# psvemmc-v12.net
KiCad netlist of a schematic drawn in EAGLE
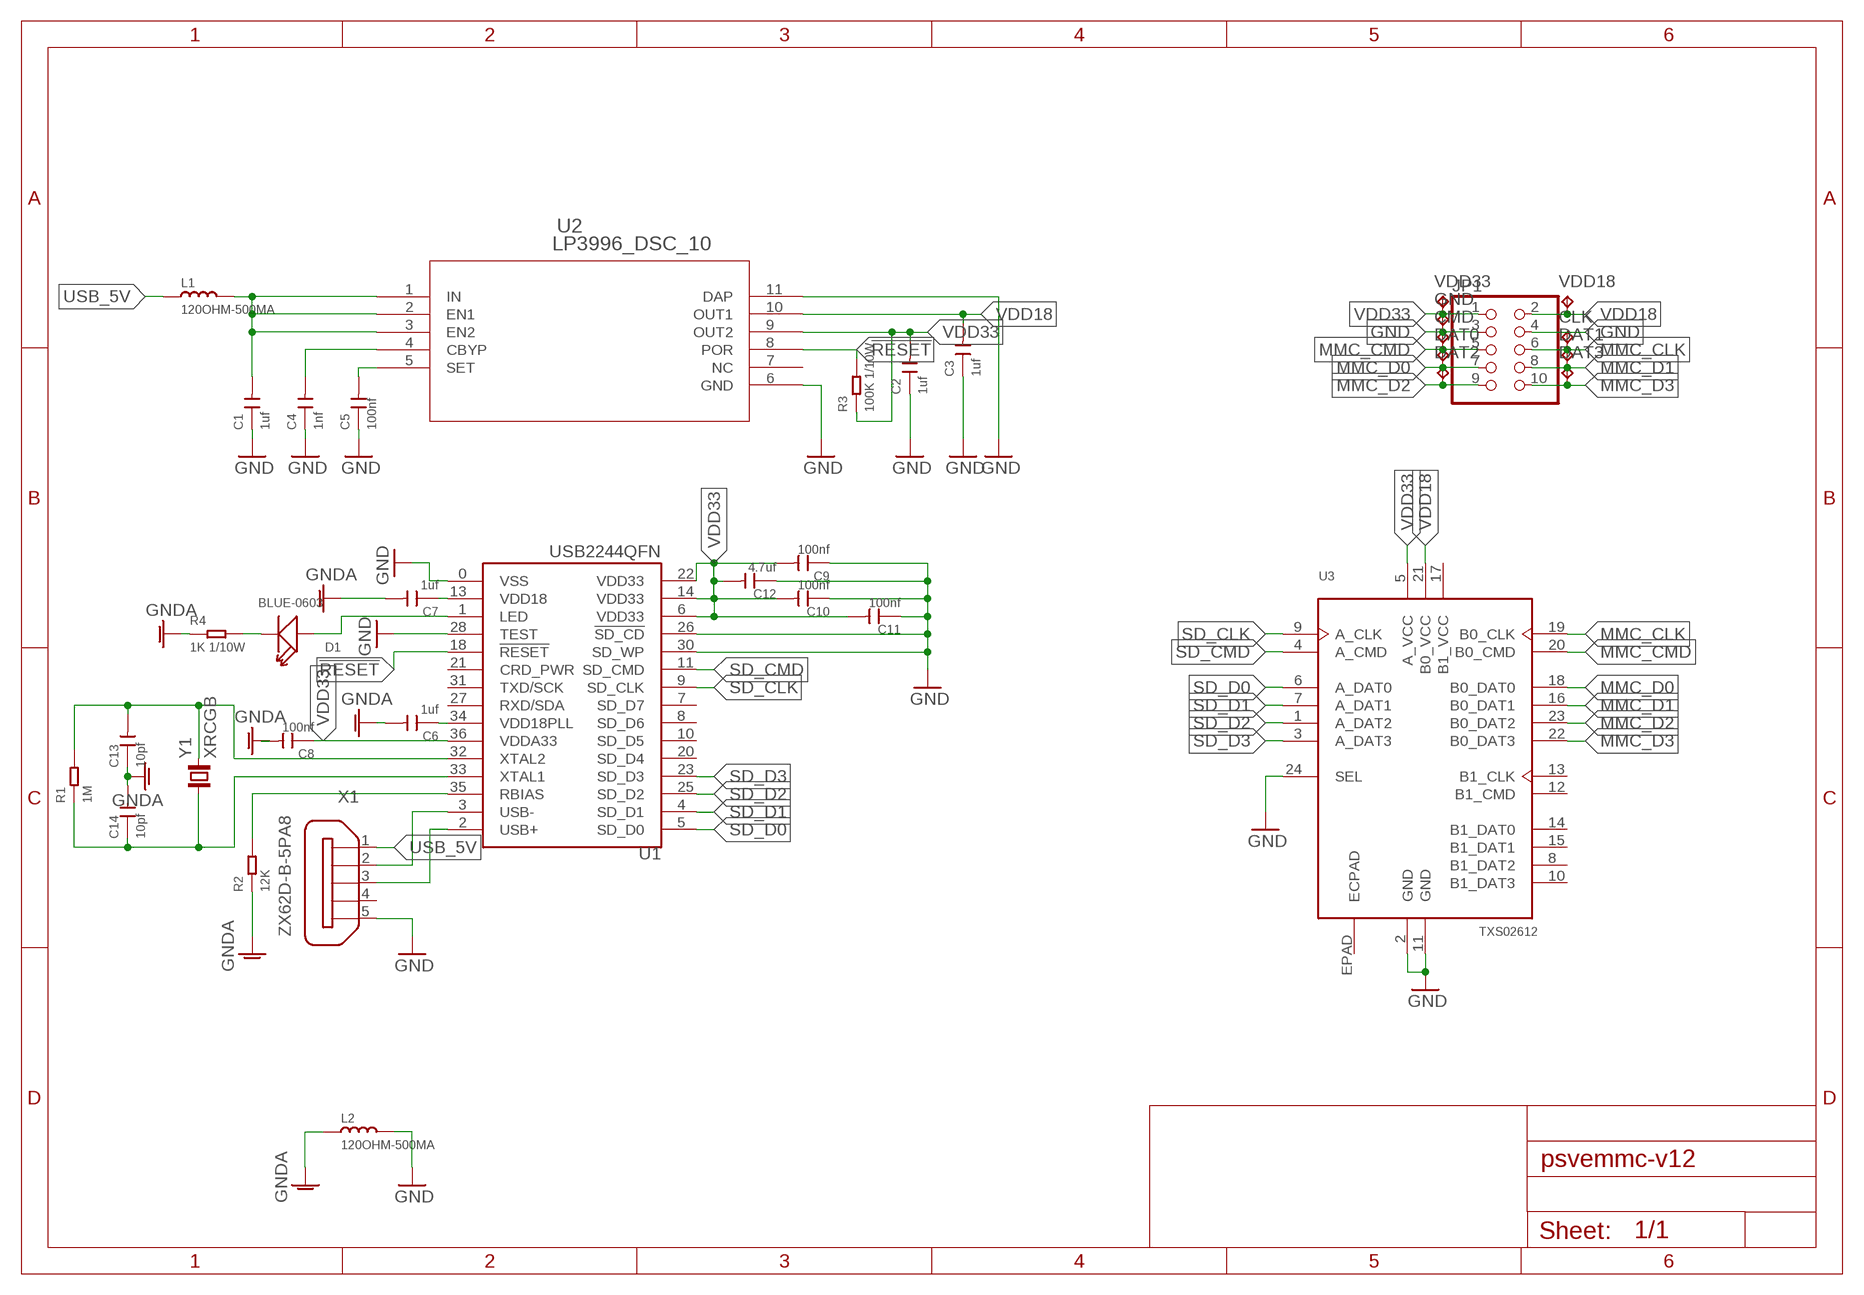
[diagram p0: schematic, sheet 1]

(export (version "E")
  (design (tool "Eeschema 10.0.6"))
  (components
    (comp (ref "C1")
      (value "1uf")
      (footprint "eagle-import:C0603")
      (fields (field (name "MPN") "CC0603KRX7R8BB105"))
      (libsource (lib "eagle-import") (part "CERAMIC-1UF-25V-10%-X7R(0603)"))
    )
    (comp (ref "C2")
      (value "1uf")
      (footprint "eagle-import:C0603")
      (fields (field (name "MPN") "CC0603KRX7R8BB105"))
      (libsource (lib "eagle-import") (part "CERAMIC-1UF-25V-10%-X7R(0603)"))
    )
    (comp (ref "C3")
      (value "1uf")
      (footprint "eagle-import:C0603")
      (fields (field (name "MPN") "CC0603KRX7R8BB105"))
      (libsource (lib "eagle-import") (part "CERAMIC-1UF-25V-10%-X7R(0603)"))
    )
    (comp (ref "C4")
      (value "1nf")
      (footprint "eagle-import:C0603")
      (fields (field (name "MPN") "GRM1885C1H102JA01D"))
      (libsource (lib "eagle-import") (part "CERAMIC-1NF-50V-5%-C0G(0603)"))
    )
    (comp (ref "C5")
      (value "100nf")
      (footprint "eagle-import:C0603")
      (fields (field (name "MPN") "CC0603KRX7R9BB104"))
      (libsource (lib "eagle-import") (part "CERAMIC-100NF-50V-10%-X7R(0603)"))
    )
    (comp (ref "C6")
      (value "1uf")
      (footprint "eagle-import:C0603")
      (fields (field (name "MPN") "CC0603KRX7R8BB105"))
      (libsource (lib "eagle-import") (part "CERAMIC-1UF-25V-10%-X7R(0603)"))
    )
    (comp (ref "C7")
      (value "1uf")
      (footprint "eagle-import:C0603")
      (fields (field (name "MPN") "CC0603KRX7R8BB105"))
      (libsource (lib "eagle-import") (part "CERAMIC-1UF-25V-10%-X7R(0603)"))
    )
    (comp (ref "C8")
      (value "100nf")
      (footprint "eagle-import:C0603")
      (fields (field (name "MPN") "CC0603KRX7R9BB104"))
      (libsource (lib "eagle-import") (part "CERAMIC-100NF-50V-10%-X7R(0603)"))
    )
    (comp (ref "C9")
      (value "100nf")
      (footprint "eagle-import:C0603")
      (fields (field (name "MPN") "CC0603KRX7R9BB104"))
      (libsource (lib "eagle-import") (part "CERAMIC-100NF-50V-10%-X7R(0603)"))
    )
    (comp (ref "C10")
      (value "100nf")
      (footprint "eagle-import:C0603")
      (fields (field (name "MPN") "CC0603KRX7R9BB104"))
      (libsource (lib "eagle-import") (part "CERAMIC-100NF-50V-10%-X7R(0603)"))
    )
    (comp (ref "C11")
      (value "100nf")
      (footprint "eagle-import:C0603")
      (fields (field (name "MPN") "CC0603KRX7R9BB104"))
      (libsource (lib "eagle-import") (part "CERAMIC-100NF-50V-10%-X7R(0603)"))
    )
    (comp (ref "C12")
      (value "4.7uf")
      (footprint "eagle-import:C0603")
      (fields (field (name "MPN") "CC0603KRX5R6BB475"))
      (libsource (lib "eagle-import") (part "CERAMIC-4.7UF-10V-10%-X5R(0603)"))
    )
    (comp (ref "C13")
      (value "10pf")
      (footprint "eagle-import:C0603")
      (fields (field (name "MPN") "CC0603JRNPO9BN100"))
      (libsource (lib "eagle-import") (part "CERAMIC-10PF-50V-5%-NPO(0603)"))
    )
    (comp (ref "C14")
      (value "10pf")
      (footprint "eagle-import:C0603")
      (fields (field (name "MPN") "CC0603JRNPO9BN100"))
      (libsource (lib "eagle-import") (part "CERAMIC-10PF-50V-5%-NPO(0603)"))
    )
    (comp (ref "CLK")
      (value "TPTP20SQ")
      (footprint "eagle-import:TP20SQ")
      (libsource (lib "eagle-import") (part "TPTP20SQ"))
    )
    (comp (ref "CMD")
      (value "TPTP20SQ")
      (footprint "eagle-import:TP20SQ")
      (libsource (lib "eagle-import") (part "TPTP20SQ"))
    )
    (comp (ref "D1")
      (value "BLUE-0603")
      (footprint "eagle-import:LED-0603")
      (fields (field (name "MPN") "19-217-BHC-ZL1M2RY-3T"))
      (libsource (lib "eagle-import") (part "SMD-LED-CLEAR-BLUE(0603)"))
    )
    (comp (ref "DAT0")
      (value "TPTP20SQ")
      (footprint "eagle-import:TP20SQ")
      (libsource (lib "eagle-import") (part "TPTP20SQ"))
    )
    (comp (ref "DAT1")
      (value "TPTP20SQ")
      (footprint "eagle-import:TP20SQ")
      (libsource (lib "eagle-import") (part "TPTP20SQ"))
    )
    (comp (ref "DAT2")
      (value "TPTP20SQ")
      (footprint "eagle-import:TP20SQ")
      (libsource (lib "eagle-import") (part "TPTP20SQ"))
    )
    (comp (ref "DAT3")
      (value "TPTP20SQ")
      (footprint "eagle-import:TP20SQ")
      (libsource (lib "eagle-import") (part "TPTP20SQ"))
    )
    (comp (ref "GND")
      (value "TPTP20SQ")
      (footprint "eagle-import:TP20SQ")
      (libsource (lib "eagle-import") (part "TPTP20SQ"))
    )
    (comp (ref "JP1")
      (value "PINHD-2X5")
      (footprint "eagle-import:2X05")
      (libsource (lib "eagle-import") (part "PINHD-2X5"))
    )
    (comp (ref "L1")
      (value "120OHM-500MA")
      (footprint "eagle-import:L0603")
      (fields (field (name "MPN") "BLM18AG121SN1D"))
      (libsource (lib "eagle-import") (part "SMD-FERRITE-CHIP-120-OHM-500MA(0603)"))
    )
    (comp (ref "L2")
      (value "120OHM-500MA")
      (footprint "eagle-import:L0603")
      (fields (field (name "MPN") "BLM18AG121SN1D"))
      (libsource (lib "eagle-import") (part "SMD-FERRITE-CHIP-120-OHM-500MA(0603)"))
    )
    (comp (ref "R1")
      (value "1M")
      (footprint "eagle-import:R0603")
      (fields (field (name "MPN") "RC0603FR-071ML"))
      (libsource (lib "eagle-import") (part "SMD-RES-1M-1%-1/10W(0603)"))
    )
    (comp (ref "R2")
      (value "12K")
      (footprint "eagle-import:R0603")
      (fields (field (name "MPN") "RC0603FR-0712KL"))
      (libsource (lib "eagle-import") (part "SMD-RES-12K-1%-1/10W(0603)"))
    )
    (comp (ref "R3")
      (value "100K 1/10W")
      (footprint "eagle-import:R0603")
      (fields (field (name "MPN") "RC0603JR-07100KL"))
      (libsource (lib "eagle-import") (part "SMD-RES-100K-5%-1/10W(0603)"))
    )
    (comp (ref "R4")
      (value "1K 1/10W")
      (footprint "eagle-import:R0603")
      (fields (field (name "MPN") "RC0603JR-071KL"))
      (libsource (lib "eagle-import") (part "SMD-RES-1K-5%-1/10W(0603)"))
    )
    (comp (ref "U1")
      (value "USB2244QFN")
      (footprint "eagle-import:QFN36")
      (libsource (lib "eagle-import") (part "USB2244QFN"))
    )
    (comp (ref "U2")
      (value "LP3996_DSC_10")
      (footprint "eagle-import:SDA10A")
      (fields (field (name "PARTNUMBER") "LP3996SD0833"))
      (libsource (lib "eagle-import") (part "LP3996_DSC_10"))
    )
    (comp (ref "U3")
      (value "TXS02612")
      (footprint "eagle-import:S-PWQFN-N24")
      (libsource (lib "eagle-import") (part "TXS02612"))
    )
    (comp (ref "VDD18")
      (value "TPTP20SQ")
      (footprint "eagle-import:TP20SQ")
      (libsource (lib "eagle-import") (part "TPTP20SQ"))
    )
    (comp (ref "VDD33")
      (value "TPTP20SQ")
      (footprint "eagle-import:TP20SQ")
      (libsource (lib "eagle-import") (part "TPTP20SQ"))
    )
    (comp (ref "X1")
      (value "ZX62D-B-5PA8")
      (footprint "eagle-import:ZX62D-B-5PA8")
      (fields (field (name "MF") "Hirose"))
      (libsource (lib "eagle-import") (part "ZX62D-B-5PA8"))
    )
    (comp (ref "Y1")
      (value "XRCGB")
      (footprint "eagle-import:XRCGB")
      (libsource (lib "eagle-import") (part "XRCGB"))
    )
  )
  (nets
    (net (code "1") (name "/B1_VCC") (class "Default")
      (node (ref "U3") (pin "17") (pinfunction "B1_VCC_17") (pintype "power_in"))
    )
    (net (code "2") (name "/ECPAD") (class "Default")
      (node (ref "U3") (pin "EPAD") (pinfunction "ECPAD_EPAD") (pintype "power_in"))
    )
    (net (code "3") (name "/~{RESET}") (class "Default")
      (node (ref "R3") (pin "2") (pinfunction "2_2") (pintype "passive"))
      (node (ref "U1") (pin "18") (pinfunction "~{RESET}_18") (pintype "input"))
      (node (ref "U2") (pin "8") (pinfunction "POR_8") (pintype "passive"))
    )
    (net (code "4") (name "GND") (class "Default")
      (node (ref "C1") (pin "1") (pinfunction "1_1") (pintype "passive"))
      (node (ref "C10") (pin "1") (pinfunction "1_1") (pintype "passive"))
      (node (ref "C11") (pin "1") (pinfunction "1_1") (pintype "passive"))
      (node (ref "C12") (pin "1") (pinfunction "1_1") (pintype "passive"))
      (node (ref "C2") (pin "1") (pinfunction "1_1") (pintype "passive"))
      (node (ref "C3") (pin "1") (pinfunction "1_1") (pintype "passive"))
      (node (ref "C4") (pin "1") (pinfunction "1_1") (pintype "passive"))
      (node (ref "C5") (pin "1") (pinfunction "1_1") (pintype "passive"))
      (node (ref "C9") (pin "1") (pinfunction "1_1") (pintype "passive"))
      (node (ref "GND") (pin "TP") (pinfunction "TP_TP") (pintype "input"))
      (node (ref "JP1") (pin "3") (pinfunction "3_3") (pintype "passive"))
      (node (ref "JP1") (pin "4") (pinfunction "4_4") (pintype "passive"))
      (node (ref "L2") (pin "2") (pinfunction "2_2") (pintype "passive"))
      (node (ref "U1") (pin "0") (pinfunction "VSS_0") (pintype "bidirectional"))
      (node (ref "U1") (pin "26") (pinfunction "~{SD_CD}_26") (pintype "bidirectional"))
      (node (ref "U1") (pin "28") (pinfunction "TEST_28") (pintype "input"))
      (node (ref "U1") (pin "30") (pinfunction "SD_WP_30") (pintype "input"))
      (node (ref "U2") (pin "11") (pinfunction "DAP_11") (pintype "passive"))
      (node (ref "U2") (pin "6") (pinfunction "GND_6") (pintype "passive"))
      (node (ref "U3") (pin "11") (pinfunction "GND_11") (pintype "power_in"))
      (node (ref "U3") (pin "2") (pinfunction "GND_2") (pintype "power_in"))
      (node (ref "U3") (pin "24") (pinfunction "SEL_24") (pintype "input"))
      (node (ref "X1") (pin "5") (pinfunction "5_5") (pintype "passive"))
    )
    (net (code "5") (name "GNDA") (class "Default")
      (node (ref "C13") (pin "1") (pinfunction "1_1") (pintype "passive"))
      (node (ref "C14") (pin "2") (pinfunction "2_2") (pintype "passive"))
      (node (ref "C6") (pin "2") (pinfunction "2_2") (pintype "passive"))
      (node (ref "C7") (pin "2") (pinfunction "2_2") (pintype "passive"))
      (node (ref "C8") (pin "2") (pinfunction "2_2") (pintype "passive"))
      (node (ref "L2") (pin "1") (pinfunction "1_1") (pintype "passive"))
      (node (ref "R2") (pin "1") (pinfunction "1_1") (pintype "passive"))
      (node (ref "R4") (pin "1") (pinfunction "1_1") (pintype "passive"))
    )
    (net (code "6") (name "MMC_CLK") (class "Default")
      (node (ref "CLK") (pin "TP") (pinfunction "TP_TP") (pintype "input"))
      (node (ref "JP1") (pin "6") (pinfunction "6_6") (pintype "passive"))
      (node (ref "U3") (pin "19") (pinfunction "B0_CLK_19") (pintype "output"))
    )
    (net (code "7") (name "MMC_CMD") (class "Default")
      (node (ref "CMD") (pin "TP") (pinfunction "TP_TP") (pintype "input"))
      (node (ref "JP1") (pin "5") (pinfunction "5_5") (pintype "passive"))
      (node (ref "U3") (pin "20") (pinfunction "B0_CMD_20") (pintype "bidirectional"))
    )
    (net (code "8") (name "MMC_D0") (class "Default")
      (node (ref "DAT0") (pin "TP") (pinfunction "TP_TP") (pintype "input"))
      (node (ref "JP1") (pin "7") (pinfunction "7_7") (pintype "passive"))
      (node (ref "U3") (pin "18") (pinfunction "B0_DAT0_18") (pintype "bidirectional"))
    )
    (net (code "9") (name "MMC_D1") (class "Default")
      (node (ref "DAT1") (pin "TP") (pinfunction "TP_TP") (pintype "input"))
      (node (ref "JP1") (pin "8") (pinfunction "8_8") (pintype "passive"))
      (node (ref "U3") (pin "16") (pinfunction "B0_DAT1_16") (pintype "bidirectional"))
    )
    (net (code "10") (name "MMC_D2") (class "Default")
      (node (ref "DAT2") (pin "TP") (pinfunction "TP_TP") (pintype "input"))
      (node (ref "JP1") (pin "9") (pinfunction "9_9") (pintype "passive"))
      (node (ref "U3") (pin "23") (pinfunction "B0_DAT2_23") (pintype "bidirectional"))
    )
    (net (code "11") (name "MMC_D3") (class "Default")
      (node (ref "DAT3") (pin "TP") (pinfunction "TP_TP") (pintype "input"))
      (node (ref "JP1") (pin "10") (pinfunction "10_10") (pintype "passive"))
      (node (ref "U3") (pin "22") (pinfunction "B0_DAT3_22") (pintype "bidirectional"))
    )
    (net (code "12") (name "Net-(D1-Pad-)") (class "Default")
      (node (ref "D1") (pin "-") (pinfunction "-_-") (pintype "passive"))
      (node (ref "R4") (pin "2") (pinfunction "2_2") (pintype "passive"))
    )
    (net (code "13") (name "Net-(U1-LED)") (class "Default")
      (node (ref "D1") (pin "+") (pinfunction "+_+") (pintype "passive"))
      (node (ref "U1") (pin "1") (pinfunction "LED_1") (pintype "bidirectional"))
    )
    (net (code "14") (name "Net-(U1-RBIAS)") (class "Default")
      (node (ref "R2") (pin "2") (pinfunction "2_2") (pintype "passive"))
      (node (ref "U1") (pin "35") (pinfunction "RBIAS_35") (pintype "bidirectional"))
    )
    (net (code "15") (name "Net-(U1-USB+)") (class "Default")
      (node (ref "U1") (pin "2") (pinfunction "USB+_2") (pintype "bidirectional"))
      (node (ref "X1") (pin "3") (pinfunction "3_3") (pintype "passive"))
    )
    (net (code "16") (name "Net-(U1-USB-)") (class "Default")
      (node (ref "U1") (pin "3") (pinfunction "USB-_3") (pintype "bidirectional"))
      (node (ref "X1") (pin "2") (pinfunction "2_2") (pintype "passive"))
    )
    (net (code "17") (name "Net-(U1-VDD18)") (class "Default")
      (node (ref "C7") (pin "1") (pinfunction "1_1") (pintype "passive"))
      (node (ref "U1") (pin "13") (pinfunction "VDD18_13") (pintype "bidirectional"))
    )
    (net (code "18") (name "Net-(U1-VDD18PLL)") (class "Default")
      (node (ref "C6") (pin "1") (pinfunction "1_1") (pintype "passive"))
      (node (ref "U1") (pin "34") (pinfunction "VDD18PLL_34") (pintype "bidirectional"))
    )
    (net (code "19") (name "Net-(U1-XTAL1)") (class "Default")
      (node (ref "C14") (pin "1") (pinfunction "1_1") (pintype "passive"))
      (node (ref "R1") (pin "1") (pinfunction "1_1") (pintype "passive"))
      (node (ref "U1") (pin "33") (pinfunction "XTAL1_33") (pintype "input"))
      (node (ref "Y1") (pin "1") (pinfunction "1_1") (pintype "passive"))
    )
    (net (code "20") (name "Net-(U1-XTAL2)") (class "Default")
      (node (ref "C13") (pin "2") (pinfunction "2_2") (pintype "passive"))
      (node (ref "R1") (pin "2") (pinfunction "2_2") (pintype "passive"))
      (node (ref "U1") (pin "32") (pinfunction "XTAL2_32") (pintype "output"))
      (node (ref "Y1") (pin "3") (pinfunction "2_3") (pintype "passive"))
    )
    (net (code "21") (name "Net-(U2-CBYP)") (class "Default")
      (node (ref "C4") (pin "2") (pinfunction "2_2") (pintype "passive"))
      (node (ref "U2") (pin "4") (pinfunction "CBYP_4") (pintype "passive"))
    )
    (net (code "22") (name "Net-(U2-EN1)") (class "Default")
      (node (ref "C1") (pin "2") (pinfunction "2_2") (pintype "passive"))
      (node (ref "L1") (pin "2") (pinfunction "2_2") (pintype "passive"))
      (node (ref "U2") (pin "1") (pinfunction "IN_1") (pintype "input"))
      (node (ref "U2") (pin "2") (pinfunction "EN1_2") (pintype "passive"))
      (node (ref "U2") (pin "3") (pinfunction "EN2_3") (pintype "passive"))
    )
    (net (code "23") (name "Net-(U2-SET)") (class "Default")
      (node (ref "C5") (pin "2") (pinfunction "2_2") (pintype "passive"))
      (node (ref "U2") (pin "5") (pinfunction "SET_5") (pintype "passive"))
    )
    (net (code "24") (name "SD_CLK") (class "Default")
      (node (ref "U1") (pin "9") (pinfunction "SD_CLK_9") (pintype "output"))
      (node (ref "U3") (pin "9") (pinfunction "A_CLK_9") (pintype "input"))
    )
    (net (code "25") (name "SD_CMD") (class "Default")
      (node (ref "U1") (pin "11") (pinfunction "SD_CMD_11") (pintype "bidirectional"))
      (node (ref "U3") (pin "4") (pinfunction "A_CMD_4") (pintype "bidirectional"))
    )
    (net (code "26") (name "SD_D0") (class "Default")
      (node (ref "U1") (pin "5") (pinfunction "SD_D0_5") (pintype "bidirectional"))
      (node (ref "U3") (pin "6") (pinfunction "A_DAT0_6") (pintype "bidirectional"))
    )
    (net (code "27") (name "SD_D1") (class "Default")
      (node (ref "U1") (pin "4") (pinfunction "SD_D1_4") (pintype "bidirectional"))
      (node (ref "U3") (pin "7") (pinfunction "A_DAT1_7") (pintype "bidirectional"))
    )
    (net (code "28") (name "SD_D2") (class "Default")
      (node (ref "U1") (pin "25") (pinfunction "SD_D2_25") (pintype "bidirectional"))
      (node (ref "U3") (pin "1") (pinfunction "A_DAT2_1") (pintype "bidirectional"))
    )
    (net (code "29") (name "SD_D3") (class "Default")
      (node (ref "U1") (pin "23") (pinfunction "SD_D3_23") (pintype "bidirectional"))
      (node (ref "U3") (pin "3") (pinfunction "A_DAT3_3") (pintype "bidirectional"))
    )
    (net (code "30") (name "USB_5V") (class "Default")
      (node (ref "L1") (pin "1") (pinfunction "1_1") (pintype "passive"))
      (node (ref "X1") (pin "1") (pinfunction "1_1") (pintype "passive"))
    )
    (net (code "31") (name "VDD18") (class "Default")
      (node (ref "C3") (pin "2") (pinfunction "2_2") (pintype "passive"))
      (node (ref "JP1") (pin "2") (pinfunction "2_2") (pintype "passive"))
      (node (ref "U2") (pin "10") (pinfunction "OUT1_10") (pintype "output"))
      (node (ref "U3") (pin "21") (pinfunction "B0_VCC_21") (pintype "power_in"))
      (node (ref "VDD18") (pin "TP") (pinfunction "TP_TP") (pintype "input"))
    )
    (net (code "32") (name "VDD33") (class "Default")
      (node (ref "C10") (pin "2") (pinfunction "2_2") (pintype "passive"))
      (node (ref "C11") (pin "2") (pinfunction "2_2") (pintype "passive"))
      (node (ref "C12") (pin "2") (pinfunction "2_2") (pintype "passive"))
      (node (ref "C2") (pin "2") (pinfunction "2_2") (pintype "passive"))
      (node (ref "C8") (pin "1") (pinfunction "1_1") (pintype "passive"))
      (node (ref "C9") (pin "2") (pinfunction "2_2") (pintype "passive"))
      (node (ref "JP1") (pin "1") (pinfunction "1_1") (pintype "passive"))
      (node (ref "R3") (pin "1") (pinfunction "1_1") (pintype "passive"))
      (node (ref "U1") (pin "14") (pinfunction "VDD33_14") (pintype "bidirectional"))
      (node (ref "U1") (pin "22") (pinfunction "VDD33_22") (pintype "bidirectional"))
      (node (ref "U1") (pin "36") (pinfunction "VDDA33_36") (pintype "bidirectional"))
      (node (ref "U1") (pin "6") (pinfunction "VDD33_6") (pintype "bidirectional"))
      (node (ref "U2") (pin "9") (pinfunction "OUT2_9") (pintype "output"))
      (node (ref "U3") (pin "5") (pinfunction "A_VCC_5") (pintype "power_in"))
      (node (ref "VDD33") (pin "TP") (pinfunction "TP_TP") (pintype "input"))
    )
    (net (code "33") (name "unconnected-(U1-CRD_PWR-Pad21)") (class "Default")
      (node (ref "U1") (pin "21") (pinfunction "CRD_PWR_21") (pintype "bidirectional"))
    )
    (net (code "34") (name "unconnected-(U1-RXD{slash}SDA-Pad27)") (class "Default")
      (node (ref "U1") (pin "27") (pinfunction "RXD/SDA_27") (pintype "bidirectional"))
    )
    (net (code "35") (name "unconnected-(U1-SD_D4-Pad20)") (class "Default")
      (node (ref "U1") (pin "20") (pinfunction "SD_D4_20") (pintype "bidirectional"))
    )
    (net (code "36") (name "unconnected-(U1-SD_D5-Pad10)") (class "Default")
      (node (ref "U1") (pin "10") (pinfunction "SD_D5_10") (pintype "bidirectional"))
    )
    (net (code "37") (name "unconnected-(U1-SD_D6-Pad8)") (class "Default")
      (node (ref "U1") (pin "8") (pinfunction "SD_D6_8") (pintype "bidirectional"))
    )
    (net (code "38") (name "unconnected-(U1-SD_D7-Pad7)") (class "Default")
      (node (ref "U1") (pin "7") (pinfunction "SD_D7_7") (pintype "bidirectional"))
    )
    (net (code "39") (name "unconnected-(U1-TXD{slash}SCK-Pad31)") (class "Default")
      (node (ref "U1") (pin "31") (pinfunction "TXD/SCK_31") (pintype "bidirectional"))
    )
    (net (code "40") (name "unconnected-(U2-NC-Pad7)") (class "Default")
      (node (ref "U2") (pin "7") (pinfunction "NC_7") (pintype "passive"))
    )
    (net (code "41") (name "unconnected-(U3-B1_CLK-Pad13)") (class "Default")
      (node (ref "U3") (pin "13") (pinfunction "B1_CLK_13") (pintype "output"))
    )
    (net (code "42") (name "unconnected-(U3-B1_CMD-Pad12)") (class "Default")
      (node (ref "U3") (pin "12") (pinfunction "B1_CMD_12") (pintype "bidirectional"))
    )
    (net (code "43") (name "unconnected-(U3-B1_DAT0-Pad14)") (class "Default")
      (node (ref "U3") (pin "14") (pinfunction "B1_DAT0_14") (pintype "bidirectional"))
    )
    (net (code "44") (name "unconnected-(U3-B1_DAT1-Pad15)") (class "Default")
      (node (ref "U3") (pin "15") (pinfunction "B1_DAT1_15") (pintype "bidirectional"))
    )
    (net (code "45") (name "unconnected-(U3-B1_DAT2-Pad8)") (class "Default")
      (node (ref "U3") (pin "8") (pinfunction "B1_DAT2_8") (pintype "bidirectional"))
    )
    (net (code "46") (name "unconnected-(U3-B1_DAT3-Pad10)") (class "Default")
      (node (ref "U3") (pin "10") (pinfunction "B1_DAT3_10") (pintype "bidirectional"))
    )
    (net (code "47") (name "unconnected-(X1-Pad4)") (class "Default")
      (node (ref "X1") (pin "4") (pinfunction "4_4") (pintype "passive"))
    )
  )
)
